# pai.net
KiCad netlist of a schematic drawn in Altium Designer
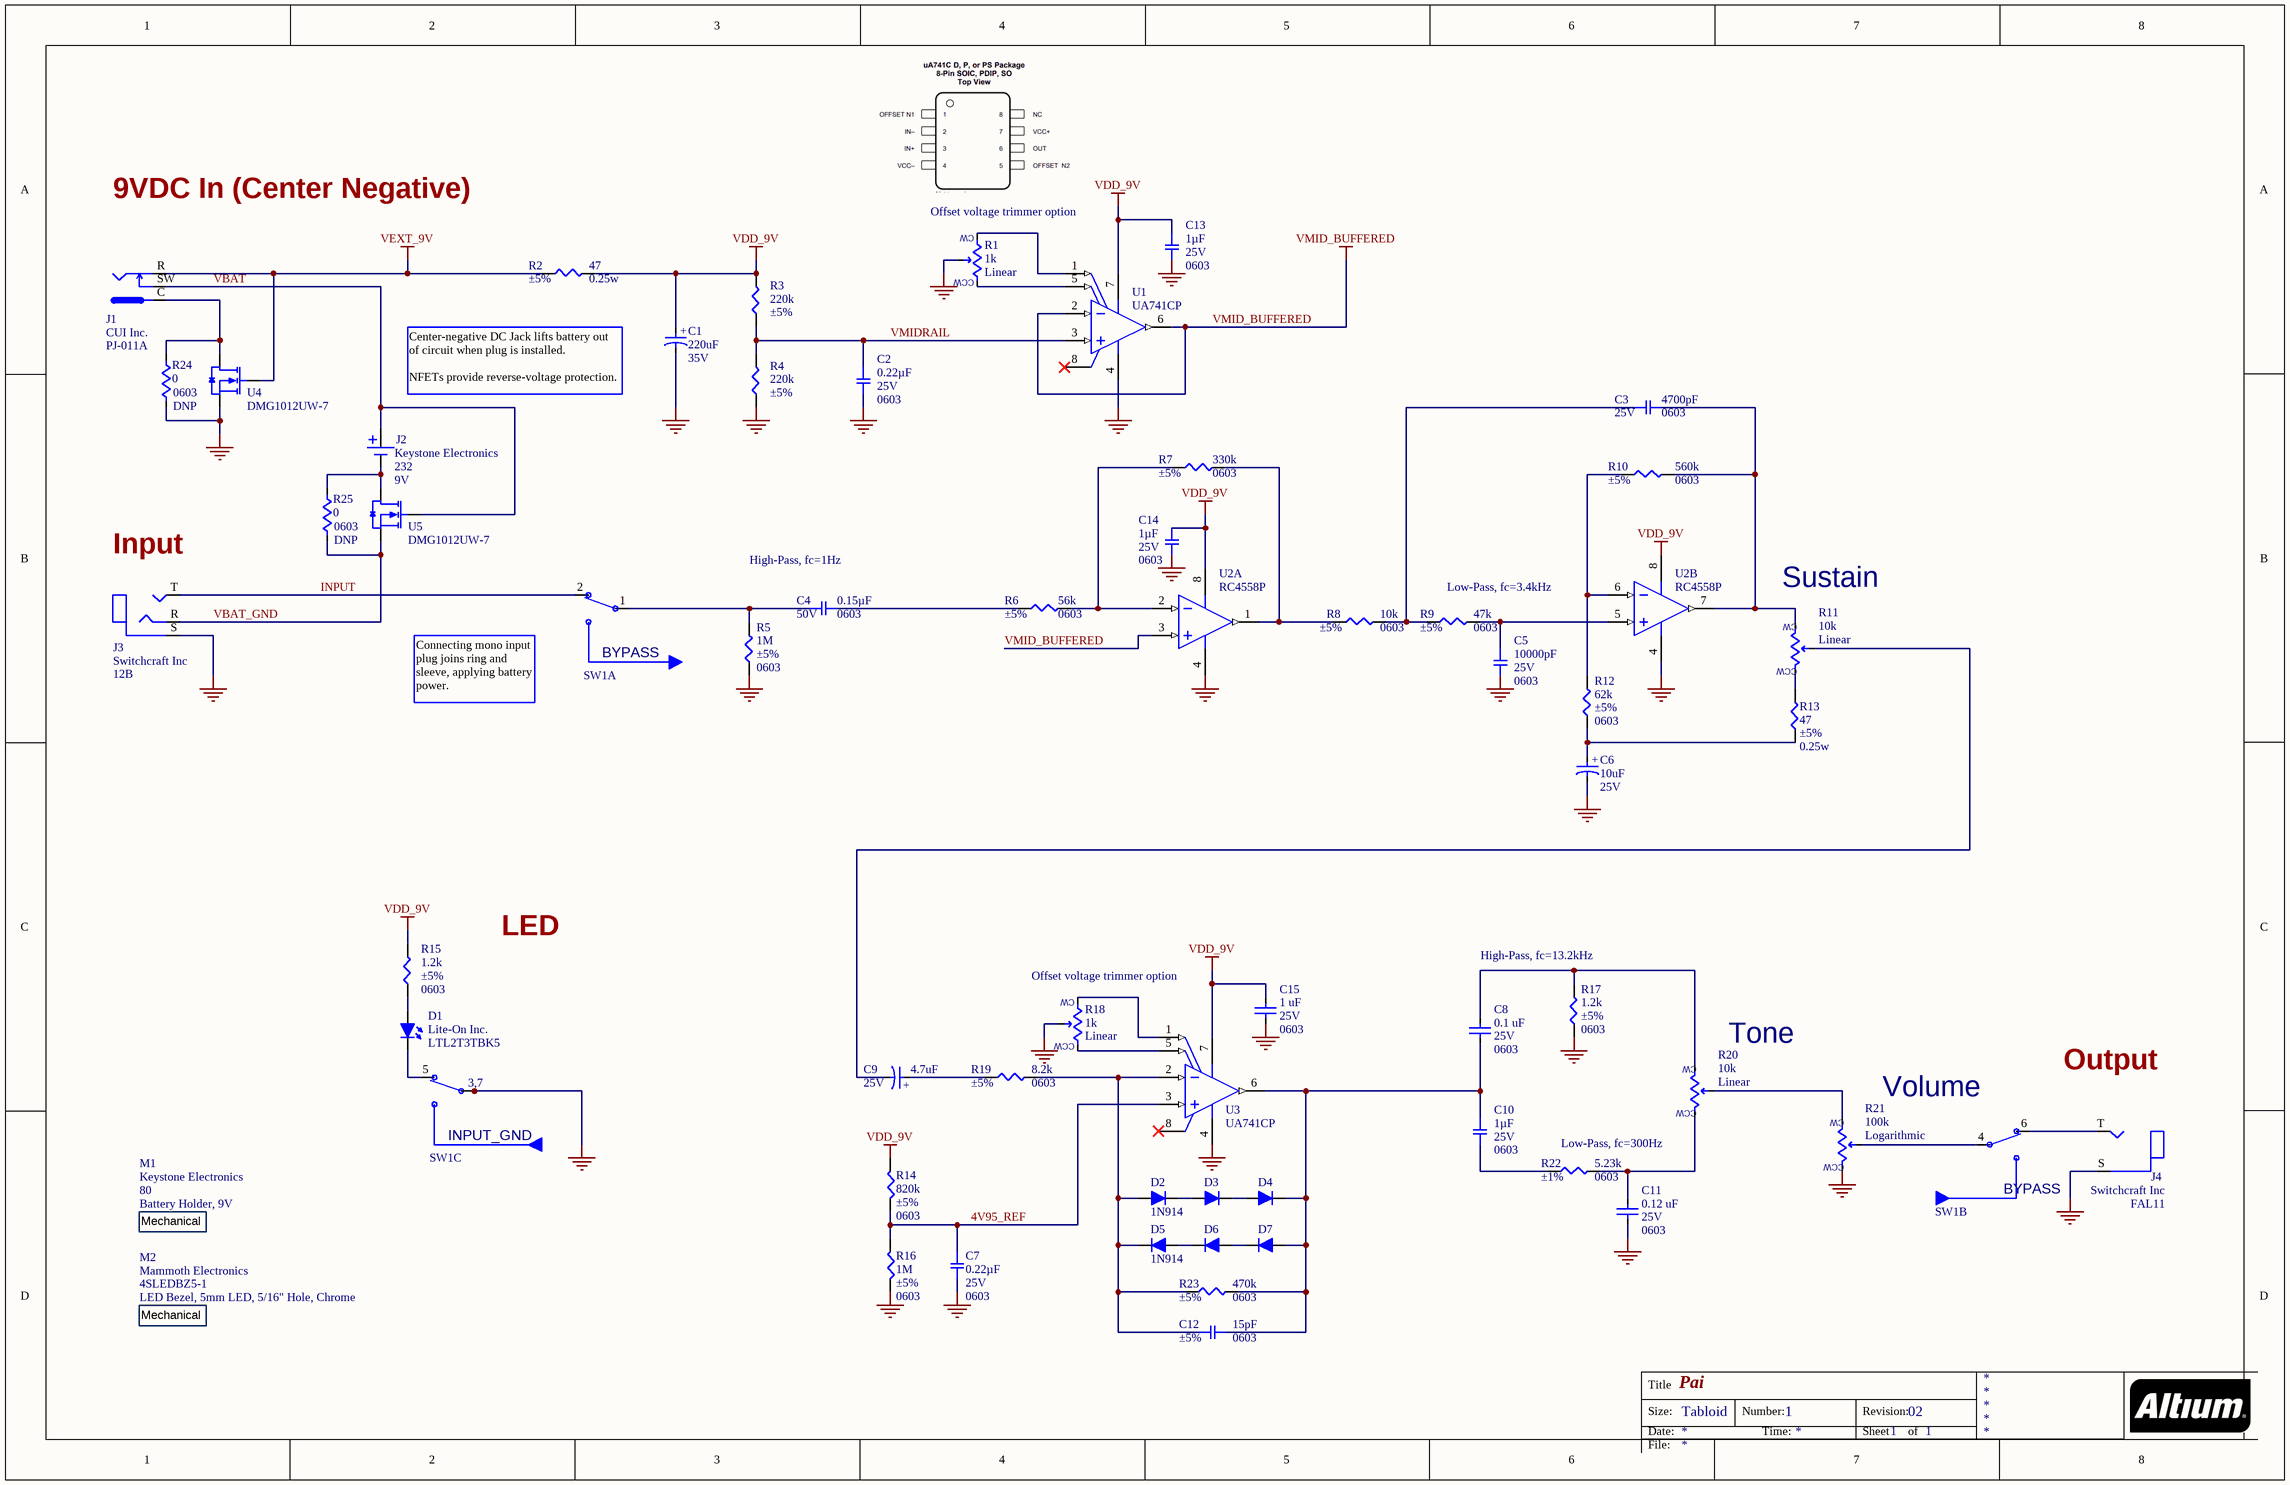
[diagram p0: pai.SchDoc]

(export (version "E")
  (design (tool "Eeschema 10.0.6"))
  (components
    (comp (ref "C1")
      (value "220uF")
      (footprint "CAP_TH_10X14_L5")
      (description "CAP ALUM 220UF 20% 35V THRU HOLE")
      (fields
        (field (name "VOLTAGE-RATED") "35V")
        (field (name "TOLERANCE") "20%")
        (field (name "Comment") "CAP-POL")
      )
      (libsource (lib "capacitors") (part "CAP-POL"))
    )
    (comp (ref "C2")
      (value "0.22µF")
      (footprint "SMD-0603C")
      (description "CAP CER 0.22UF 25V X7R 0603")
      (fields
        (field (name "PART NUMBER") "GRM188R71E224KA88D")
        (field (name "DIGI-KEY PART NUMBER") "490-3290-1-ND")
        (field (name "VOLTAGE") "25V")
        (field (name "PACKAGE / CASE") "0603")
      )
      (libsource (lib "cap_murata") (part "CAPACITOR"))
    )
    (comp (ref "C3")
      (value "4700pF")
      (footprint "SMD-0603C")
      (description "CAP CER 4700PF 25V X7R 0603")
      (fields
        (field (name "PART NUMBER") "GCM188R71E472KA37D")
        (field (name "DIGI-KEY PART NUMBER") "490-11959-1-ND")
        (field (name "VOLTAGE") "25V")
        (field (name "PACKAGE / CASE") "0603")
      )
      (libsource (lib "cap_murata") (part "CAPACITOR"))
    )
    (comp (ref "C4")
      (value "0.15µF")
      (footprint "SMD-0603C")
      (description "CAP CER 0.15UF 50V X7R 0603")
      (fields
        (field (name "PART NUMBER") "GCM188R71H154KA64D")
        (field (name "DIGI-KEY PART NUMBER") "490-11960-1-ND")
        (field (name "VOLTAGE") "50V")
        (field (name "PACKAGE / CASE") "0603")
      )
      (libsource (lib "cap_murata") (part "CAPACITOR"))
    )
    (comp (ref "C5")
      (value "10000pF")
      (footprint "SMD-0603C")
      (description "CAP CER 10000PF 25V X7R 0603")
      (fields
        (field (name "PART NUMBER") "GRM188R71E103KA01J")
        (field (name "DIGI-KEY PART NUMBER") "490-11997-1-ND")
        (field (name "VOLTAGE") "25V")
        (field (name "PACKAGE / CASE") "0603")
      )
      (libsource (lib "cap_murata") (part "CAPACITOR"))
    )
    (comp (ref "C6")
      (value "10uF")
      (footprint "CAP_TH_5X12_L5")
      (description "CAP ALUM 10UF 20% 25V RADIAL")
      (fields
        (field (name "VOLTAGE-RATED") "25V")
        (field (name "TOLERANCE") "20%")
        (field (name "Comment") "CAP-POL")
      )
      (libsource (lib "capacitors") (part "CAP-POL"))
    )
    (comp (ref "C7")
      (value "0.22µF")
      (footprint "SMD-0603C")
      (description "CAP CER 0.22UF 25V X7R 0603")
      (fields
        (field (name "PART NUMBER") "GRM188R71E224KA88D")
        (field (name "DIGI-KEY PART NUMBER") "490-3290-1-ND")
        (field (name "VOLTAGE") "25V")
        (field (name "PACKAGE / CASE") "0603")
      )
      (libsource (lib "cap_murata") (part "CAPACITOR"))
    )
    (comp (ref "C8")
      (value "0.1 uF")
      (footprint "CAPC1608X09N")
      (description "CAP CER 0.1UF 25V X5R 0603")
      (fields
        (field (name "TOLERANCE") "20%")
        (field (name "VOLTAGE-RATED") "25V")
        (field (name "PACKAGE / CASE") "0603")
        (field (name "Comment") "CAP")
      )
      (libsource (lib "capacitors") (part "CAP"))
    )
    (comp (ref "C9")
      (value "4.7uF")
      (footprint "CAP_TH_5X12_L2")
      (description "CAP ALUM 4.7UF 20% 25V RADIAL")
      (fields
        (field (name "VOLTAGE-RATED") "25V")
        (field (name "TOLERANCE") "20%")
        (field (name "Comment") "CAP-POL")
      )
      (libsource (lib "") (part "CAP-POL_1"))
    )
    (comp (ref "C10")
      (value "1µF")
      (footprint "SMD-0603C")
      (description "CAP CER 1UF 25V X7R 0603")
      (fields
        (field (name "PART NUMBER") "GRM188R71E105KA12D")
        (field (name "DIGI-KEY PART NUMBER") "490-5307-1-ND")
        (field (name "VOLTAGE") "25V")
        (field (name "PACKAGE / CASE") "0603")
      )
      (libsource (lib "cap_murata") (part "CAPACITOR"))
    )
    (comp (ref "C11")
      (value "0.12 uF")
      (footprint "CAPC1608X09N")
      (description "CAP CER 0.12UF 25V X7R 0603")
      (fields
        (field (name "TOLERANCE") "10%")
        (field (name "VOLTAGE-RATED") "25V")
        (field (name "PACKAGE / CASE") "0603")
        (field (name "Comment") "CAP")
      )
      (libsource (lib "capacitors") (part "CAP"))
    )
    (comp (ref "C12")
      (value "15pF")
      (footprint "SMD-0603C")
      (description "CAP CER 15PF 50V NP0 0603")
      (fields
        (field (name "PART NUMBER") "GCM1885C1H150JA16D")
        (field (name "DIGI-KEY PART NUMBER") "490-4957-1-ND")
        (field (name "TOLERANCE") "±5%")
        (field (name "PACKAGE / CASE") "0603")
      )
      (libsource (lib "cap_murata") (part "CAPACITOR"))
    )
    (comp (ref "C13")
      (value "1µF")
      (footprint "SMD-0603C")
      (description "CAP CER 1UF 25V X7R 0603")
      (fields
        (field (name "PART NUMBER") "GRM188R71E105KA12D")
        (field (name "DIGI-KEY PART NUMBER") "490-5307-1-ND")
        (field (name "VOLTAGE") "25V")
        (field (name "PACKAGE / CASE") "0603")
      )
      (libsource (lib "cap_murata") (part "CAPACITOR"))
    )
    (comp (ref "C14")
      (value "1µF")
      (footprint "SMD-0603C")
      (description "CAP CER 1UF 25V X7R 0603")
      (fields
        (field (name "PART NUMBER") "GRM188R71E105KA12D")
        (field (name "DIGI-KEY PART NUMBER") "490-5307-1-ND")
        (field (name "VOLTAGE") "25V")
        (field (name "PACKAGE / CASE") "0603")
      )
      (libsource (lib "cap_murata") (part "CAPACITOR"))
    )
    (comp (ref "C15")
      (value "1 uF")
      (footprint "CAPC1608X09N")
      (description "CAP CER 1UF 25V X5R 0603")
      (fields
        (field (name "TOLERANCE") "10%")
        (field (name "VOLTAGE-RATED") "25V")
        (field (name "PACKAGE / CASE") "0603")
        (field (name "Comment") "CAP")
      )
      (libsource (lib "capacitors") (part "CAP"))
    )
    (comp (ref "D1")
      (value "LED-Blue")
      (footprint "LED_TH_5MM_BLUE")
      (description "LED BLUE CLEAR T-1 3/4 T/H")
      (fields (field (name "MANUFACTURER 1") "Lite-On Inc.") (field (name "MANUFACTURER 1 PN") "LTL2T3TBK5"))
      (libsource (lib "diodes") (part "LED-Blue"))
    )
    (comp (ref "D2")
      (value "DIO-GEN")
      (footprint "DO35-2_1N914")
      (description "DIODE GEN PURP 75V 200MA DO35")
      (fields (field (name "MANUFACTURER 1 PN") "1N914"))
      (libsource (lib "diodes") (part "DIO-GEN"))
    )
    (comp (ref "D3")
      (value "DIO-GEN")
      (footprint "DO35-2_1N914")
      (description "DIODE GEN PURP 75V 200MA DO35")
      (libsource (lib "diodes") (part "DIO-GEN"))
    )
    (comp (ref "D4")
      (value "DIO-GEN")
      (footprint "DO35-2_1N914")
      (description "DIODE GEN PURP 75V 200MA DO35")
      (libsource (lib "diodes") (part "DIO-GEN"))
    )
    (comp (ref "D5")
      (value "DIO-GEN")
      (footprint "DO35-2_1N914")
      (description "DIODE GEN PURP 75V 200MA DO35")
      (fields (field (name "MANUFACTURER 1 PN") "1N914"))
      (libsource (lib "diodes") (part "DIO-GEN"))
    )
    (comp (ref "D6")
      (value "DIO-GEN")
      (footprint "DO35-2_1N914")
      (description "DIODE GEN PURP 75V 200MA DO35")
      (libsource (lib "diodes") (part "DIO-GEN"))
    )
    (comp (ref "D7")
      (value "DIO-GEN")
      (footprint "DO35-2_1N914")
      (description "DIODE GEN PURP 75V 200MA DO35")
      (libsource (lib "diodes") (part "DIO-GEN"))
    )
    (comp (ref "J1")
      (value "PWR_JACK_SW")
      (footprint "PWR_JACK_SW_HDR")
      (description "CONN PWR JACK 2X5.5MM SOLDER")
      (fields (field (name "MANUFACTURER 1 PN") "PJ-011A") (field (name "MANUFACTURER 1") "CUI Inc."))
      (libsource (lib "connectors") (part "PWR_JACK_SW"))
    )
    (comp (ref "J2")
      (value "9V_BATT")
      (footprint "PWR_JACK_HDR")
      (description "BATTERY CONNECT SNAP 9V 4\" LEADS")
      (fields
        (field (name "MANUFACTURER 1 PN") "232")
        (field (name "BATTERY CELL SIZE") "9V")
        (field (name "MANUFACTURER 1") "Keystone Electronics")
      )
      (libsource (lib "connectors") (part "9V_BATT"))
    )
    (comp (ref "J3")
      (value "STEREO_JACK")
      (footprint "STEREO_JACK_HDR")
      (description "CONN JACK STEREO 6.35MM PNL MNT")
      (fields (field (name "MANUFACTURER 1 PN") "12B") (field (name "MANUFACTURER 1") "Switchcraft Inc"))
      (libsource (lib "connectors") (part "STEREO_JACK"))
    )
    (comp (ref "J4")
      (value "MONO_JACK")
      (footprint "MONO_JACK_HDR")
      (description "CONN JACK MONO 6.35MM PNL MNT")
      (fields (field (name "MANUFACTURER 1 PN") "FAL11") (field (name "MANUFACTURER 1") "Switchcraft Inc"))
      (libsource (lib "connectors") (part "MONO_JACK"))
    )
    (comp (ref "M1")
      (value "MECH")
      (description "BATTERY HOLDER CLIP 9V")
      (fields
        (field (name "MANUFACTURER 1 PN") "80")
        (field (name "MANUFACTURER 1") "Keystone Electronics")
        (field (name "DESC") "Battery Holder, 9V")
      )
      (libsource (lib "mechanical") (part "MECH"))
    )
    (comp (ref "M2")
      (value "MECH")
      (description "LED Bezel, 5mm LED, 5/16\" Hole, Chrome")
      (fields
        (field (name "MANUFACTURER 1 PN") "4SLEDBZ5-1")
        (field (name "SUPPLIER 1") "Mammoth Electronics")
        (field (name "DESC") "LED Bezel, 5mm LED, 5/16\" Hole, Chrome")
      )
      (libsource (lib "mechanical") (part "MECH"))
    )
    (comp (ref "R1")
      (value "1k")
      (footprint "POT_TT35W")
      (description "Potentiometer, 1k, Linear Taper, Trim, Single Gang, Surface Mount")
      (fields (field (name "TAPER") "Linear") (field (name "TOLERANCE") "25%") (field (name "Comment") "POT"))
      (libsource (lib "electromechanical") (part "POT"))
    )
    (comp (ref "R2")
      (value "47")
      (footprint "SMD-0603-RES")
      (description "RES SMD 47 OHM 5% 1/4W 0603")
      (fields
        (field (name "PART NUMBER") "ERJ-PA3J470V")
        (field (name "DIGI-KEY PART NUMBER") "P47.00BZCT-ND")
        (field (name "TOLERANCE") "±5%")
        (field (name "POWER (WATTS)") "0.25w")
      )
      (libsource (lib "res_panasonic_erj_xls") (part "RESISTOR"))
    )
    (comp (ref "R3")
      (value "220k")
      (footprint "SMD-0603-RES")
      (description "RES SMD 220K OHM 5% 1/4W 0603")
      (fields
        (field (name "PART NUMBER") "ERJ-PA3J224V")
        (field (name "DIGI-KEY PART NUMBER") "P220KBZCT-ND")
        (field (name "TOLERANCE") "±5%")
      )
      (libsource (lib "res_panasonic_erj_xls") (part "RESISTOR"))
    )
    (comp (ref "R4")
      (value "220k")
      (footprint "SMD-0603-RES")
      (description "RES SMD 220K OHM 5% 1/4W 0603")
      (fields
        (field (name "PART NUMBER") "ERJ-PA3J224V")
        (field (name "DIGI-KEY PART NUMBER") "P220KBZCT-ND")
        (field (name "TOLERANCE") "±5%")
      )
      (libsource (lib "res_panasonic_erj_xls") (part "RESISTOR"))
    )
    (comp (ref "R5")
      (value "1M")
      (footprint "SMD-0603-RES")
      (description "RES SMD 1M OHM 5% 1/10W 0603")
      (fields
        (field (name "PART NUMBER") "ERJ-3GEYJ105V")
        (field (name "DIGI-KEY PART NUMBER") "P1.0MGCT-ND")
        (field (name "TOLERANCE") "±5%")
        (field (name "SUPPLIER DEVICE PACKAGE") "0603")
      )
      (libsource (lib "res_panasonic_erj_xls") (part "RESISTOR"))
    )
    (comp (ref "R6")
      (value "56k")
      (footprint "SMD-0603-RES")
      (description "RES SMD 56K OHM 5% 1/10W 0603")
      (fields
        (field (name "PART NUMBER") "ERJ-3GEYJ563V")
        (field (name "DIGI-KEY PART NUMBER") "P56KGCT-ND")
        (field (name "TOLERANCE") "±5%")
        (field (name "SUPPLIER DEVICE PACKAGE") "0603")
      )
      (libsource (lib "res_panasonic_erj_xls") (part "RESISTOR"))
    )
    (comp (ref "R7")
      (value "330k")
      (footprint "SMD-0603-RES")
      (description "RES SMD 330K OHM 5% 1/10W 0603")
      (fields
        (field (name "PART NUMBER") "ERJ-3GEYJ334V")
        (field (name "DIGI-KEY PART NUMBER") "P330KGCT-ND")
        (field (name "TOLERANCE") "±5%")
        (field (name "SUPPLIER DEVICE PACKAGE") "0603")
      )
      (libsource (lib "res_panasonic_erj_xls") (part "RESISTOR"))
    )
    (comp (ref "R8")
      (value "10k")
      (footprint "SMD-0603-RES")
      (description "RES SMD 10K OHM 5% 1/10W 0603")
      (fields
        (field (name "PART NUMBER") "ERJ-3GEYJ103V")
        (field (name "DIGI-KEY PART NUMBER") "P10KGCT-ND")
        (field (name "TOLERANCE") "±5%")
        (field (name "SUPPLIER DEVICE PACKAGE") "0603")
      )
      (libsource (lib "res_panasonic_erj_xls") (part "RESISTOR"))
    )
    (comp (ref "R9")
      (value "47k")
      (footprint "SMD-0603-RES")
      (description "RES SMD 47K OHM 5% 1/10W 0603")
      (fields
        (field (name "PART NUMBER") "ERJ-3GEYJ473V")
        (field (name "DIGI-KEY PART NUMBER") "P47KGCT-ND")
        (field (name "TOLERANCE") "±5%")
        (field (name "PACKAGE / CASE") "0603")
      )
      (libsource (lib "res_panasonic_erj_xls") (part "RESISTOR"))
    )
    (comp (ref "R10")
      (value "560k")
      (footprint "SMD-0603-RES")
      (description "RES SMD 560K OHM 5% 1/10W 0603")
      (fields
        (field (name "PART NUMBER") "ERJ-3GEYJ564V")
        (field (name "DIGI-KEY PART NUMBER") "P560KGCT-ND")
        (field (name "TOLERANCE") "±5%")
        (field (name "SUPPLIER DEVICE PACKAGE") "0603")
      )
      (libsource (lib "res_panasonic_erj_xls") (part "RESISTOR"))
    )
    (comp (ref "R11")
      (value "10k")
      (footprint "POT_16MM_TH_RA")
      (description "Potentiometer, 10k, Linear Taper, 16mm, Single Gang, TH RA")
      (fields (field (name "TAPER") "Linear") (field (name "TOLERANCE") "5%") (field (name "Comment") "POT"))
      (libsource (lib "electromechanical") (part "POT"))
    )
    (comp (ref "R12")
      (value "62k")
      (footprint "SMD-0603-RES")
      (description "RES SMD 62K OHM 5% 1/10W 0603")
      (fields
        (field (name "PART NUMBER") "ERJ-3GEYJ623V")
        (field (name "DIGI-KEY PART NUMBER") "P62KGCT-ND")
        (field (name "TOLERANCE") "±5%")
        (field (name "SUPPLIER DEVICE PACKAGE") "0603")
      )
      (libsource (lib "res_panasonic_erj_xls") (part "RESISTOR"))
    )
    (comp (ref "R13")
      (value "47")
      (footprint "SMD-0603-RES")
      (description "RES SMD 47 OHM 5% 1/4W 0603")
      (fields
        (field (name "PART NUMBER") "ERJ-PA3J470V")
        (field (name "DIGI-KEY PART NUMBER") "P47.00BZCT-ND")
        (field (name "TOLERANCE") "±5%")
        (field (name "POWER (WATTS)") "0.25w")
      )
      (libsource (lib "res_panasonic_erj_xls") (part "RESISTOR"))
    )
    (comp (ref "R14")
      (value "820k")
      (footprint "SMD-0603-RES")
      (description "RES SMD 820K OHM 5% 1/10W 0603")
      (fields
        (field (name "PART NUMBER") "ERJ-3GEYJ824V")
        (field (name "DIGI-KEY PART NUMBER") "P820KGCT-ND")
        (field (name "TOLERANCE") "±5%")
        (field (name "SUPPLIER DEVICE PACKAGE") "0603")
      )
      (libsource (lib "res_panasonic_erj_xls") (part "RESISTOR"))
    )
    (comp (ref "R15")
      (value "1.2k")
      (footprint "SMD-0603-RES")
      (description "RES SMD 1.2K OHM 5% 1/10W 0603")
      (fields
        (field (name "PART NUMBER") "ERJ-3GEYJ122V")
        (field (name "DIGI-KEY PART NUMBER") "P1.2KGCT-ND")
        (field (name "TOLERANCE") "±5%")
        (field (name "PACKAGE / CASE") "0603")
      )
      (libsource (lib "res_panasonic_erj_xls") (part "RESISTOR"))
    )
    (comp (ref "R16")
      (value "1M")
      (footprint "SMD-0603-RES")
      (description "RES SMD 1M OHM 5% 1/10W 0603")
      (fields
        (field (name "PART NUMBER") "ERJ-3GEYJ105V")
        (field (name "DIGI-KEY PART NUMBER") "P1.0MGCT-ND")
        (field (name "TOLERANCE") "±5%")
        (field (name "SUPPLIER DEVICE PACKAGE") "0603")
      )
      (libsource (lib "res_panasonic_erj_xls") (part "RESISTOR"))
    )
    (comp (ref "R17")
      (value "1.2k")
      (footprint "SMD-0603-RES")
      (description "RES SMD 1.2K OHM 5% 1/10W 0603")
      (fields
        (field (name "PART NUMBER") "ERJ-3GEYJ122V")
        (field (name "DIGI-KEY PART NUMBER") "P1.2KGCT-ND")
        (field (name "TOLERANCE") "±5%")
        (field (name "SUPPLIER DEVICE PACKAGE") "0603")
      )
      (libsource (lib "res_panasonic_erj_xls") (part "RESISTOR"))
    )
    (comp (ref "R18")
      (value "1k")
      (footprint "POT_TT35W")
      (description "Potentiometer, 1k, Linear Taper, Trim, Single Gang, Surface Mount")
      (fields (field (name "TAPER") "Linear") (field (name "TOLERANCE") "25%") (field (name "Comment") "POT"))
      (libsource (lib "electromechanical") (part "POT"))
    )
    (comp (ref "R19")
      (value "8.2k")
      (footprint "SMD-0603-RES")
      (description "RES SMD 8.2K OHM 5% 1/10W 0603")
      (fields
        (field (name "PART NUMBER") "ERJ-3GEYJ822V")
        (field (name "DIGI-KEY PART NUMBER") "P8.2KGCT-ND")
        (field (name "TOLERANCE") "±5%")
        (field (name "SUPPLIER DEVICE PACKAGE") "0603")
      )
      (libsource (lib "res_panasonic_erj_xls") (part "RESISTOR"))
    )
    (comp (ref "R20")
      (value "10k")
      (footprint "POT_16MM_TH_RA")
      (description "Potentiometer, 10k, Linear Taper, 16mm, Single Gang, TH RA")
      (fields (field (name "TAPER") "Linear") (field (name "TOLERANCE") "5%") (field (name "Comment") "POT"))
      (libsource (lib "electromechanical") (part "POT"))
    )
    (comp (ref "R21")
      (value "100k")
      (footprint "POT_16MM_TH_RA")
      (description "Potentiometer, 100k, Log Taper, 16mm, Single Gang, TH RA")
      (fields
        (field (name "TAPER") "Logarithmic")
        (field (name "TOLERANCE") "5%")
        (field (name "Comment") "POT")
      )
      (libsource (lib "electromechanical") (part "POT"))
    )
    (comp (ref "R22")
      (value "5.23k")
      (footprint "SMD-0603-RES")
      (description "RES SMD 5.23K OHM 1% 1/10W 0603")
      (fields
        (field (name "PART NUMBER") "ERJ-3EKF5231V")
        (field (name "DIGI-KEY PART NUMBER") "P5.23KHCT-ND")
        (field (name "TOLERANCE") "±1%")
        (field (name "SUPPLIER DEVICE PACKAGE") "0603")
      )
      (libsource (lib "res_panasonic_erj_xls") (part "RESISTOR"))
    )
    (comp (ref "R23")
      (value "470k")
      (footprint "SMD-0603-RES")
      (description "RES SMD 470K OHM 5% 1/10W 0603")
      (fields
        (field (name "PART NUMBER") "ERJ-3GEYJ474V")
        (field (name "DIGI-KEY PART NUMBER") "P470KGCT-ND")
        (field (name "TOLERANCE") "±5%")
        (field (name "SUPPLIER DEVICE PACKAGE") "0603")
      )
      (libsource (lib "res_panasonic_erj_xls") (part "RESISTOR"))
    )
    (comp (ref "R24")
      (value "0")
      (footprint "RESC1508X09N")
      (description "RES 0 OHM JUMPER 1/10W 0603")
      (fields (field (name "PACKAGE") "0603") (field (name "DNP") "DNP") (field (name "Comment") "RES"))
      (libsource (lib "resistors") (part "RES"))
    )
    (comp (ref "R25")
      (value "0")
      (footprint "RESC1508X09N")
      (description "RES 0 OHM JUMPER 1/10W 0603")
      (fields (field (name "PACKAGE") "0603") (field (name "DNP") "DNP") (field (name "Comment") "RES"))
      (libsource (lib "resistors") (part "RES"))
    )
    (comp (ref "SW1")
      (value "3PDT_SW_SOLDERBOARD")
      (libsource (lib "3PDT_SW_SOLDERBOARD") (part "3PDT_SW_SOLDERBOARD"))
    )
    (comp (ref "U1")
      (value "UA741CP")
      (footprint "TI-P8")
      (description "General-Purpose Operational Amplifier, 7 to 36 V, 0 to 70 degC, 8-pin DIP (P8), Pb-Free (RoHS)")
      (fields (field (name "MANUFACTURER") "Texas Instruments"))
      (libsource (lib "TI Amplifiers and Linear Operational Amplifier General Purpose") (part "UA741CP"))
    )
    (comp (ref "U2")
      (value "RC4558P")
      (footprint "TI-P8")
      (fields (field (name "MANUFACTURER") "Texas Instruments"))
      (libsource (lib "TI Amplifiers and Linear Operational Amplifier General Purpose") (part "RC4558P"))
    )
    (comp (ref "U3")
      (value "UA741CP")
      (footprint "TI-P8")
      (description "General-Purpose Operational Amplifier, 7 to 36 V, 0 to 70 degC, 8-pin DIP (P8), Pb-Free (RoHS)")
      (fields (field (name "MANUFACTURER") "Texas Instruments"))
      (libsource (lib "TI Amplifiers and Linear Operational Amplifier General Purpose") (part "UA741CP"))
    )
    (comp (ref "U4")
      (value "NFET_SOT323")
      (footprint "SOT65P205X110-3N_DMG1012UW-7")
      (description "MOSFET N-CH 20V 1A SOT323")
      (fields
        (field (name "MANUFACTURER") "Diodes Incorporated")
        (field (name "MANUFACTURER PART NUMBER") "DMG1012UW-7")
      )
      (libsource (lib "discretes") (part "NFET_SOT323"))
    )
    (comp (ref "U5")
      (value "NFET_SOT323")
      (footprint "SOT65P205X110-3N_DMG1012UW-7")
      (description "MOSFET N-CH 20V 1A SOT323")
      (fields
        (field (name "MANUFACTURER") "Diodes Incorporated")
        (field (name "MANUFACTURER PART NUMBER") "DMG1012UW-7")
      )
      (libsource (lib "discretes") (part "NFET_SOT323"))
    )
  )
  (nets
    (net (code "1") (name "/4V95_REF") (class "Default")
      (node (ref "C7") (pin "1") (pinfunction "1_1") (pintype "passive"))
      (node (ref "R14") (pin "1") (pinfunction "1_1") (pintype "passive"))
      (node (ref "R16") (pin "2") (pinfunction "2_2") (pintype "passive"))
      (node (ref "U3") (pin "3") (pinfunction "IN+_3") (pintype "input"))
    )
    (net (code "2") (name "/INPUT") (class "Default")
      (node (ref "J3") (pin "T") (pinfunction "T_T") (pintype "passive"))
      (node (ref "SW1") (pin "2") (pinfunction "2_2") (pintype "passive"))
    )
    (net (code "3") (name "/VBAT") (class "Default")
      (node (ref "J1") (pin "SW") (pinfunction "SW_SW") (pintype "passive"))
      (node (ref "J2") (pin "1") (pinfunction "1_1") (pintype "passive"))
      (node (ref "U5") (pin "G") (pinfunction "G_G") (pintype "passive"))
    )
    (net (code "4") (name "/VBAT_GND") (class "Default")
      (node (ref "J3") (pin "R") (pinfunction "R_R") (pintype "passive"))
      (node (ref "R25") (pin "1") (pinfunction "1_1") (pintype "passive"))
      (node (ref "U5") (pin "S") (pinfunction "S_S") (pintype "passive"))
    )
    (net (code "5") (name "/VMIDRAIL") (class "Default")
      (node (ref "C2") (pin "1") (pinfunction "1_1") (pintype "passive"))
      (node (ref "R3") (pin "1") (pinfunction "1_1") (pintype "passive"))
      (node (ref "R4") (pin "2") (pinfunction "2_2") (pintype "passive"))
      (node (ref "U1") (pin "3") (pinfunction "IN+_3") (pintype "input"))
    )
    (net (code "6") (name "GND") (class "Default")
      (node (ref "C1") (pin "2") (pinfunction "2_2") (pintype "passive"))
      (node (ref "C11") (pin "2") (pinfunction "2_2") (pintype "passive"))
      (node (ref "C13") (pin "2") (pinfunction "2_2") (pintype "passive"))
      (node (ref "C14") (pin "2") (pinfunction "2_2") (pintype "passive"))
      (node (ref "C15") (pin "2") (pinfunction "2_2") (pintype "passive"))
      (node (ref "C2") (pin "2") (pinfunction "2_2") (pintype "passive"))
      (node (ref "C5") (pin "2") (pinfunction "2_2") (pintype "passive"))
      (node (ref "C6") (pin "2") (pinfunction "2_2") (pintype "passive"))
      (node (ref "C7") (pin "2") (pinfunction "2_2") (pintype "passive"))
      (node (ref "J3") (pin "S") (pinfunction "S_S") (pintype "passive"))
      (node (ref "J4") (pin "S") (pinfunction "S_S") (pintype "passive"))
      (node (ref "R1") (pin "2") (pinfunction "2_2") (pintype "passive"))
      (node (ref "R16") (pin "1") (pinfunction "1_1") (pintype "passive"))
      (node (ref "R17") (pin "1") (pinfunction "1_1") (pintype "passive"))
      (node (ref "R18") (pin "2") (pinfunction "2_2") (pintype "passive"))
      (node (ref "R21") (pin "1") (pinfunction "1_1") (pintype "passive"))
      (node (ref "R24") (pin "1") (pinfunction "1_1") (pintype "passive"))
      (node (ref "R4") (pin "1") (pinfunction "1_1") (pintype "passive"))
      (node (ref "R5") (pin "1") (pinfunction "1_1") (pintype "passive"))
      (node (ref "SW1") (pin "3") (pinfunction "3_3") (pintype "passive"))
      (node (ref "SW1") (pin "7") (pinfunction "7_7") (pintype "passive"))
      (node (ref "U1") (pin "4") (pinfunction "VCC-_4") (pintype "power_in"))
      (node (ref "U2") (pin "4") (pinfunction "VCC-_4") (pintype "power_in"))
      (node (ref "U3") (pin "4") (pinfunction "VCC-_4") (pintype "power_in"))
      (node (ref "U4") (pin "S") (pinfunction "S_S") (pintype "passive"))
    )
    (net (code "7") (name "Net-(C3-Pad1)") (class "Default")
      (node (ref "C3") (pin "1") (pinfunction "1_1") (pintype "passive"))
      (node (ref "R8") (pin "2") (pinfunction "2_2") (pintype "passive"))
      (node (ref "R9") (pin "1") (pinfunction "1_1") (pintype "passive"))
    )
    (net (code "8") (name "Net-(C4-Pad1)") (class "Default")
      (node (ref "C4") (pin "1") (pinfunction "1_1") (pintype "passive"))
      (node (ref "R5") (pin "2") (pinfunction "2_2") (pintype "passive"))
      (node (ref "SW1") (pin "1") (pinfunction "1_1") (pintype "passive"))
    )
    (net (code "9") (name "Net-(C4-Pad2)") (class "Default")
      (node (ref "C4") (pin "2") (pinfunction "2_2") (pintype "passive"))
      (node (ref "R6") (pin "1") (pinfunction "1_1") (pintype "passive"))
    )
    (net (code "10") (name "Net-(C6-Pad1)") (class "Default")
      (node (ref "C6") (pin "1") (pinfunction "1_1") (pintype "passive"))
      (node (ref "R12") (pin "1") (pinfunction "1_1") (pintype "passive"))
      (node (ref "R13") (pin "1") (pinfunction "1_1") (pintype "passive"))
    )
    (net (code "11") (name "Net-(C8-Pad1)") (class "Default")
      (node (ref "C8") (pin "1") (pinfunction "1_1") (pintype "passive"))
      (node (ref "R17") (pin "2") (pinfunction "2_2") (pintype "passive"))
      (node (ref "R20") (pin "3") (pinfunction "3_3") (pintype "passive"))
    )
    (net (code "12") (name "Net-(C9-Pad1)") (class "Default")
      (node (ref "C9") (pin "1") (pinfunction "1_1") (pintype "passive"))
      (node (ref "R19") (pin "1") (pinfunction "1_1") (pintype "passive"))
    )
    (net (code "13") (name "Net-(C9-Pad2)") (class "Default")
      (node (ref "C9") (pin "2") (pinfunction "2_2") (pintype "passive"))
      (node (ref "R11") (pin "2") (pinfunction "2_2") (pintype "passive"))
    )
    (net (code "14") (name "Net-(C10-Pad2)") (class "Default")
      (node (ref "C10") (pin "2") (pinfunction "2_2") (pintype "passive"))
      (node (ref "R22") (pin "1") (pinfunction "1_1") (pintype "passive"))
    )
    (net (code "15") (name "Net-(C11-Pad1)") (class "Default")
      (node (ref "C11") (pin "1") (pinfunction "1_1") (pintype "passive"))
      (node (ref "R20") (pin "1") (pinfunction "1_1") (pintype "passive"))
      (node (ref "R22") (pin "2") (pinfunction "2_2") (pintype "passive"))
    )
    (net (code "16") (name "Net-(D1-PadA)") (class "Default")
      (node (ref "D1") (pin "A") (pinfunction "A_A") (pintype "passive"))
      (node (ref "R15") (pin "1") (pinfunction "1_1") (pintype "passive"))
    )
    (net (code "17") (name "Net-(D1-PadK)") (class "Default")
      (node (ref "D1") (pin "K") (pinfunction "K_K") (pintype "passive"))
      (node (ref "SW1") (pin "5") (pinfunction "5_5") (pintype "passive"))
    )
    (net (code "18") (name "Net-(D2-PadK)") (class "Default")
      (node (ref "D2") (pin "K") (pinfunction "K_K") (pintype "passive"))
      (node (ref "D3") (pin "A") (pinfunction "A_A") (pintype "passive"))
    )
    (net (code "19") (name "Net-(D3-PadK)") (class "Default")
      (node (ref "D3") (pin "K") (pinfunction "K_K") (pintype "passive"))
      (node (ref "D4") (pin "A") (pinfunction "A_A") (pintype "passive"))
    )
    (net (code "20") (name "Net-(D5-PadA)") (class "Default")
      (node (ref "D5") (pin "A") (pinfunction "A_A") (pintype "passive"))
      (node (ref "D6") (pin "K") (pinfunction "K_K") (pintype "passive"))
    )
    (net (code "21") (name "Net-(D6-PadA)") (class "Default")
      (node (ref "D6") (pin "A") (pinfunction "A_A") (pintype "passive"))
      (node (ref "D7") (pin "K") (pinfunction "K_K") (pintype "passive"))
    )
    (net (code "22") (name "Net-(J1-PadC)") (class "Default")
      (node (ref "J1") (pin "C") (pinfunction "C_C") (pintype "passive"))
      (node (ref "R24") (pin "2") (pinfunction "2_2") (pintype "passive"))
      (node (ref "U4") (pin "D") (pinfunction "D_D") (pintype "passive"))
    )
    (net (code "23") (name "Net-(J2-Pad2)") (class "Default")
      (node (ref "J2") (pin "2") (pinfunction "2_2") (pintype "passive"))
      (node (ref "R25") (pin "2") (pinfunction "2_2") (pintype "passive"))
      (node (ref "U5") (pin "D") (pinfunction "D_D") (pintype "passive"))
    )
    (net (code "24") (name "Net-(J4-PadT)") (class "Default")
      (node (ref "J4") (pin "T") (pinfunction "T_T") (pintype "passive"))
      (node (ref "SW1") (pin "6") (pinfunction "6_6") (pintype "passive"))
    )
    (net (code "25") (name "Net-(R11-Pad1)") (class "Default")
      (node (ref "R11") (pin "1") (pinfunction "1_1") (pintype "passive"))
      (node (ref "R13") (pin "2") (pinfunction "2_2") (pintype "passive"))
    )
    (net (code "26") (name "Net-(R20-Pad2)") (class "Default")
      (node (ref "R20") (pin "2") (pinfunction "2_2") (pintype "passive"))
      (node (ref "R21") (pin "3") (pinfunction "3_3") (pintype "passive"))
    )
    (net (code "27") (name "Net-(R21-Pad2)") (class "Default")
      (node (ref "R21") (pin "2") (pinfunction "2_2") (pintype "passive"))
      (node (ref "SW1") (pin "4") (pinfunction "4_4") (pintype "passive"))
    )
    (net (code "28") (name "Net-(U1-OFFSET_N1)") (class "Default")
      (node (ref "R1") (pin "3") (pinfunction "3_3") (pintype "passive"))
      (node (ref "U1") (pin "1") (pinfunction "OFFSET_N1_1") (pintype "input"))
    )
    (net (code "29") (name "Net-(U1-OFFSET_N2)") (class "Default")
      (node (ref "R1") (pin "1") (pinfunction "1_1") (pintype "passive"))
      (node (ref "U1") (pin "5") (pinfunction "OFFSET_N2_5") (pintype "input"))
    )
    (net (code "30") (name "Net-(U2A-IN1-)") (class "Default")
      (node (ref "R6") (pin "2") (pinfunction "2_2") (pintype "passive"))
      (node (ref "R7") (pin "1") (pinfunction "1_1") (pintype "passive"))
      (node (ref "U2") (pin "2") (pinfunction "IN1-_2") (pintype "input"))
    )
    (net (code "31") (name "Net-(U2A-OUT1)") (class "Default")
      (node (ref "R7") (pin "2") (pinfunction "2_2") (pintype "passive"))
      (node (ref "R8") (pin "1") (pinfunction "1_1") (pintype "passive"))
      (node (ref "U2") (pin "1") (pinfunction "OUT1_1") (pintype "output"))
    )
    (net (code "32") (name "Net-(U2B-IN2+)") (class "Default")
      (node (ref "C5") (pin "1") (pinfunction "1_1") (pintype "passive"))
      (node (ref "R9") (pin "2") (pinfunction "2_2") (pintype "passive"))
      (node (ref "U2") (pin "5") (pinfunction "IN2+_5") (pintype "input"))
    )
    (net (code "33") (name "Net-(U2B-IN2-)") (class "Default")
      (node (ref "R10") (pin "1") (pinfunction "1_1") (pintype "passive"))
      (node (ref "R12") (pin "2") (pinfunction "2_2") (pintype "passive"))
      (node (ref "U2") (pin "6") (pinfunction "IN2-_6") (pintype "input"))
    )
    (net (code "34") (name "Net-(U2B-OUT2)") (class "Default")
      (node (ref "C3") (pin "2") (pinfunction "2_2") (pintype "passive"))
      (node (ref "R10") (pin "2") (pinfunction "2_2") (pintype "passive"))
      (node (ref "R11") (pin "3") (pinfunction "3_3") (pintype "passive"))
      (node (ref "U2") (pin "7") (pinfunction "OUT2_7") (pintype "output"))
    )
    (net (code "35") (name "Net-(U3-IN-)") (class "Default")
      (node (ref "C12") (pin "1") (pinfunction "1_1") (pintype "passive"))
      (node (ref "D2") (pin "A") (pinfunction "A_A") (pintype "passive"))
      (node (ref "D5") (pin "K") (pinfunction "K_K") (pintype "passive"))
      (node (ref "R19") (pin "2") (pinfunction "2_2") (pintype "passive"))
      (node (ref "R23") (pin "1") (pinfunction "1_1") (pintype "passive"))
      (node (ref "U3") (pin "2") (pinfunction "IN-_2") (pintype "input"))
    )
    (net (code "36") (name "Net-(U3-OFFSET_N1)") (class "Default")
      (node (ref "R18") (pin "3") (pinfunction "3_3") (pintype "passive"))
      (node (ref "U3") (pin "1") (pinfunction "OFFSET_N1_1") (pintype "input"))
    )
    (net (code "37") (name "Net-(U3-OFFSET_N2)") (class "Default")
      (node (ref "R18") (pin "1") (pinfunction "1_1") (pintype "passive"))
      (node (ref "U3") (pin "5") (pinfunction "OFFSET_N2_5") (pintype "input"))
    )
    (net (code "38") (name "Net-(U3-OUT)") (class "Default")
      (node (ref "C10") (pin "1") (pinfunction "1_1") (pintype "passive"))
      (node (ref "C12") (pin "2") (pinfunction "2_2") (pintype "passive"))
      (node (ref "C8") (pin "2") (pinfunction "2_2") (pintype "passive"))
      (node (ref "D4") (pin "K") (pinfunction "K_K") (pintype "passive"))
      (node (ref "D7") (pin "A") (pinfunction "A_A") (pintype "passive"))
      (node (ref "R23") (pin "2") (pinfunction "2_2") (pintype "passive"))
      (node (ref "U3") (pin "6") (pinfunction "OUT_6") (pintype "output"))
    )
    (net (code "39") (name "VDD_9V") (class "Default")
      (node (ref "C1") (pin "1") (pinfunction "1_1") (pintype "passive"))
      (node (ref "C13") (pin "1") (pinfunction "1_1") (pintype "passive"))
      (node (ref "C14") (pin "1") (pinfunction "1_1") (pintype "passive"))
      (node (ref "C15") (pin "1") (pinfunction "1_1") (pintype "passive"))
      (node (ref "R14") (pin "2") (pinfunction "2_2") (pintype "passive"))
      (node (ref "R15") (pin "2") (pinfunction "2_2") (pintype "passive"))
      (node (ref "R2") (pin "2") (pinfunction "2_2") (pintype "passive"))
      (node (ref "R3") (pin "2") (pinfunction "2_2") (pintype "passive"))
      (node (ref "U1") (pin "7") (pinfunction "VCC+_7") (pintype "power_in"))
      (node (ref "U2") (pin "8") (pinfunction "VCC+_8") (pintype "power_in"))
      (node (ref "U3") (pin "7") (pinfunction "VCC+_7") (pintype "power_in"))
    )
    (net (code "40") (name "VEXT_9V") (class "Default")
      (node (ref "J1") (pin "R") (pinfunction "R_R") (pintype "passive"))
      (node (ref "R2") (pin "1") (pinfunction "1_1") (pintype "passive"))
      (node (ref "U4") (pin "G") (pinfunction "G_G") (pintype "passive"))
    )
    (net (code "41") (name "VMID_BUFFERED") (class "Default")
      (node (ref "U1") (pin "2") (pinfunction "IN-_2") (pintype "input"))
      (node (ref "U1") (pin "6") (pinfunction "OUT_6") (pintype "output"))
      (node (ref "U2") (pin "3") (pinfunction "IN1+_3") (pintype "input"))
    )
    (net (code "42") (name "unconnected-(U1-NC-Pad8)") (class "Default")
      (node (ref "U1") (pin "8") (pinfunction "NC_8") (pintype "passive+no_connect"))
    )
    (net (code "43") (name "unconnected-(U3-NC-Pad8)") (class "Default")
      (node (ref "U3") (pin "8") (pinfunction "NC_8") (pintype "passive+no_connect"))
    )
  )
)
